# MPU6050_Gyro_Accel_Temp.net
KiCad netlist of a schematic drawn in Altium Designer
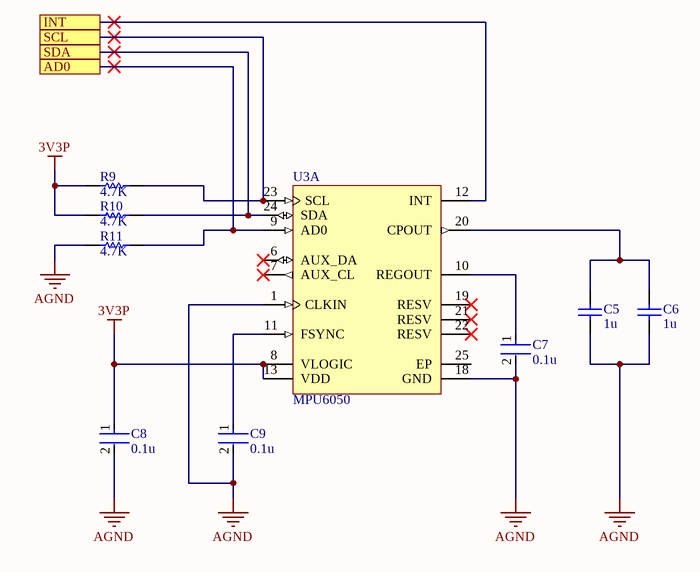
[diagram p0: MPU6050_Gyro_Accel_Temp.SchDoc]

(export (version "E")
  (design (tool "Eeschema 10.0.6"))
  (components
    (comp (ref "C5")
      (value "1u")
      (footprint "CAPC3216X110X50LL20T25")
      (description "Chip Capacitor, 1 uF, +/- 10%, 50 V, -55 to 125 degC, 1206 (3216 Metric), RoHS, Tape and Reel")
      (fields (field (name "MANUFACTURER") "Kemet") (field (name "TOLERANCE") "10%"))
      (libsource (lib "Altium Content Vault") (part "CAP-NP-2"))
    )
    (comp (ref "C6")
      (value "1u")
      (footprint "CAPC3216X110X50LL20T25")
      (description "Chip Capacitor, 1 uF, +/- 10%, 50 V, -55 to 125 degC, 1206 (3216 Metric), RoHS, Tape and Reel")
      (fields (field (name "MANUFACTURER") "Kemet") (field (name "TOLERANCE") "10%"))
      (libsource (lib "Altium Content Vault") (part "CAP-NP-2"))
    )
    (comp (ref "C7")
      (value "0.1u")
      (footprint "FP-C0402-BB-MFG")
      (description "CAP CER 0.1UF 10V X5R 0402")
      (fields (field (name "MANUFACTURER") "Kemet") (field (name "TOLERANCE") "0.1"))
      (libsource (lib "Altium Content Vault") (part "b4654b650e69147ec39a6b967a45e02"))
    )
    (comp (ref "C8")
      (value "0.1u")
      (footprint "FP-C0402-BB-MFG")
      (description "CAP CER 0.1UF 10V X5R 0402")
      (fields (field (name "MANUFACTURER") "Kemet") (field (name "TOLERANCE") "0.1"))
      (libsource (lib "Altium Content Vault") (part "b4654b650e69147ec39a6b967a45e02"))
    )
    (comp (ref "C9")
      (value "0.1u")
      (footprint "FP-C0402-BB-MFG")
      (description "CAP CER 0.1UF 10V X5R 0402")
      (fields (field (name "MANUFACTURER") "Kemet") (field (name "TOLERANCE") "0.1"))
      (libsource (lib "Altium Content Vault") (part "b4654b650e69147ec39a6b967a45e02"))
    )
    (comp (ref "R9")
      (value "4.7K")
      (footprint "RESC3216X70X50LL05T20")
      (fields (field (name "PART NUMBER") "ERJ8ENF4701V") (field (name "MANUFACTURER") "Panasonic"))
      (libsource (lib "Altium Content Vault") (part "RES"))
    )
    (comp (ref "R10")
      (value "4.7K")
      (footprint "RESC3216X70X50LL05T20")
      (fields (field (name "PART NUMBER") "ERJ8ENF4701V") (field (name "MANUFACTURER") "Panasonic"))
      (libsource (lib "Altium Content Vault") (part "RES"))
    )
    (comp (ref "R11")
      (value "4.7K")
      (footprint "RESC3216X70X50LL05T20")
      (fields (field (name "PART NUMBER") "ERJ8ENF4701V") (field (name "MANUFACTURER") "Panasonic"))
      (libsource (lib "Altium Content Vault") (part "RES"))
    )
    (comp (ref "U3")
      (value "MPU6050")
      (footprint "INSE-QFN-24_V")
      (fields (field (name "TOLERANCE") "1%"))
      (libsource (lib "Altium Content Vault") (part "INSE-MPU6050-QFN-24"))
    )
  )
  (nets
    (net (code "1") (name "/AD0") (class "Default")
      (node (ref "R11") (pin "2") (pinfunction "2_2") (pintype "passive"))
      (node (ref "U3") (pin "9") (pinfunction "AD0_9") (pintype "input"))
    )
    (net (code "2") (name "/INT") (class "Default")
      (node (ref "U3") (pin "12") (pinfunction "INT_12") (pintype "open_collector"))
    )
    (net (code "3") (name "/SCL") (class "Default")
      (node (ref "R9") (pin "2") (pinfunction "2_2") (pintype "passive"))
      (node (ref "U3") (pin "23") (pinfunction "SCL_23") (pintype "input"))
    )
    (net (code "4") (name "/SDA") (class "Default")
      (node (ref "R10") (pin "2") (pinfunction "2_2") (pintype "passive"))
      (node (ref "U3") (pin "24") (pinfunction "SDA_24") (pintype "bidirectional"))
    )
    (net (code "5") (name "3V3P") (class "Default")
      (node (ref "C8") (pin "1") (pinfunction "1_1") (pintype "passive"))
      (node (ref "R10") (pin "1") (pinfunction "1_1") (pintype "passive"))
      (node (ref "R9") (pin "1") (pinfunction "1_1") (pintype "passive"))
      (node (ref "U3") (pin "13") (pinfunction "VDD_13") (pintype "power_in"))
      (node (ref "U3") (pin "8") (pinfunction "VLOGIC_8") (pintype "power_in"))
    )
    (net (code "6") (name "AGND") (class "Default")
      (node (ref "C5") (pin "1") (pinfunction "1_1") (pintype "passive"))
      (node (ref "C6") (pin "1") (pinfunction "1_1") (pintype "passive"))
      (node (ref "C7") (pin "2") (pinfunction "2_2") (pintype "passive"))
      (node (ref "C8") (pin "2") (pinfunction "2_2") (pintype "passive"))
      (node (ref "C9") (pin "2") (pinfunction "2_2") (pintype "passive"))
      (node (ref "R11") (pin "1") (pinfunction "1_1") (pintype "passive"))
      (node (ref "U3") (pin "1") (pinfunction "CLKIN_1") (pintype "input"))
      (node (ref "U3") (pin "18") (pinfunction "GND_18") (pintype "power_in"))
    )
    (net (code "7") (name "Net-(U3A-CPOUT)") (class "Default")
      (node (ref "C5") (pin "2") (pinfunction "2_2") (pintype "passive"))
      (node (ref "C6") (pin "2") (pinfunction "2_2") (pintype "passive"))
      (node (ref "U3") (pin "20") (pinfunction "CPOUT_20") (pintype "output"))
    )
    (net (code "8") (name "Net-(U3A-FSYNC)") (class "Default")
      (node (ref "C9") (pin "1") (pinfunction "1_1") (pintype "passive"))
      (node (ref "U3") (pin "11") (pinfunction "FSYNC_11") (pintype "input"))
    )
    (net (code "9") (name "Net-(U3A-REGOUT)") (class "Default")
      (node (ref "C7") (pin "1") (pinfunction "1_1") (pintype "passive"))
      (node (ref "U3") (pin "10") (pinfunction "REGOUT_10") (pintype "passive"))
    )
    (net (code "10") (name "unconnected-(U3A-AUX_CL-Pad7)") (class "Default")
      (node (ref "U3") (pin "7") (pinfunction "AUX_CL_7") (pintype "output+no_connect"))
    )
    (net (code "11") (name "unconnected-(U3A-AUX_DA-Pad6)") (class "Default")
      (node (ref "U3") (pin "6") (pinfunction "AUX_DA_6") (pintype "bidirectional+no_connect"))
    )
    (net (code "12") (name "unconnected-(U3A-EP-Pad25)") (class "Default")
      (node (ref "U3") (pin "25") (pinfunction "EP_25") (pintype "passive"))
    )
    (net (code "13") (name "unconnected-(U3A-RESV-Pad19)") (class "Default")
      (node (ref "U3") (pin "19") (pinfunction "RESV_19") (pintype "passive+no_connect"))
    )
    (net (code "14") (name "unconnected-(U3A-RESV-Pad21)") (class "Default")
      (node (ref "U3") (pin "21") (pinfunction "RESV_21") (pintype "passive+no_connect"))
    )
    (net (code "15") (name "unconnected-(U3A-RESV-Pad22)") (class "Default")
      (node (ref "U3") (pin "22") (pinfunction "RESV_22") (pintype "passive+no_connect"))
    )
  )
)
